# LiPoBattery.net
KiCad netlist of a schematic drawn in Altium Designer
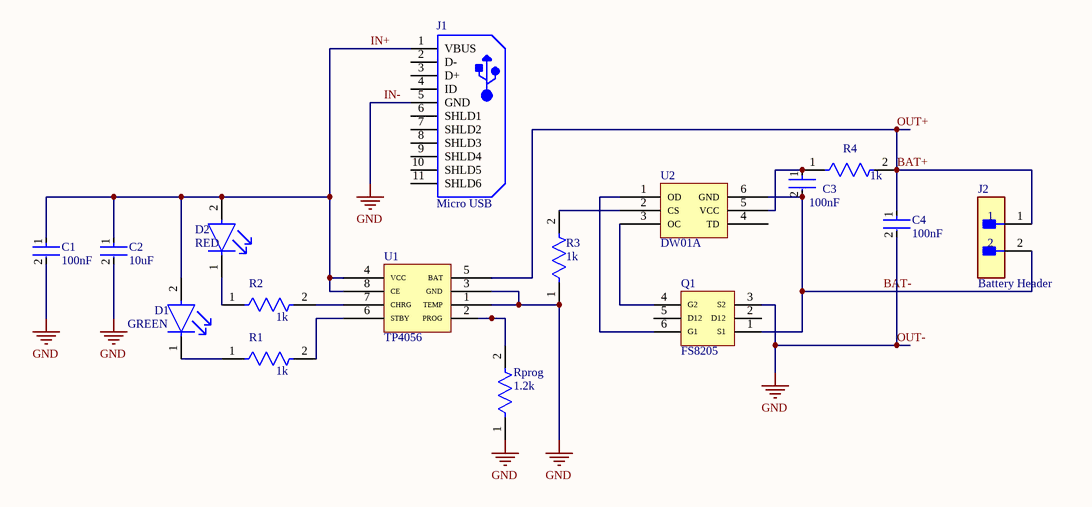
[diagram p0: LiPoBattery.SchDoc]

(export (version "E")
  (design (tool "Eeschema 10.0.6"))
  (components
    (comp (ref "C1")
      (value "100nF")
      (footprint "FP-CGA3E-0_3-0_1-IPC_B")
      (description "Cap Ceramic 100nF 25V X8R 20% Pad SMD 0603 +150°C Automotive T/R")
      (fields (field (name "TOLERANCE") "20%"))
      (libsource (lib "Altium Content Vault") (part "b4654b650e69147ec39a6b967a45e02"))
    )
    (comp (ref "C2")
      (value "10uF")
      (footprint "FP-CGA4J-IPC_B")
      (description "Cap Ceramic 10uF 10V X5R 20% Pad SMD 0805 +85°C Automotive T/R")
      (fields (field (name "TOLERANCE") "20%"))
      (libsource (lib "Altium Content Vault") (part "b4654b650e69147ec39a6b967a45e02"))
    )
    (comp (ref "C3")
      (value "100nF")
      (footprint "FP-CGA3E-0_3-0_1-IPC_B")
      (description "Cap Ceramic 100nF 25V X8R 20% Pad SMD 0603 +150°C Automotive T/R")
      (fields (field (name "TOLERANCE") "20%"))
      (libsource (lib "Altium Content Vault") (part "b4654b650e69147ec39a6b967a45e02"))
    )
    (comp (ref "C4")
      (value "100nF")
      (footprint "FP-CGA3E-0_3-0_1-IPC_B")
      (description "Cap Ceramic 100nF 25V X8R 20% Pad SMD 0603 +150°C Automotive T/R")
      (fields (field (name "TOLERANCE") "20%"))
      (libsource (lib "Altium Content Vault") (part "b4654b650e69147ec39a6b967a45e02"))
    )
    (comp (ref "D1")
      (value "GREEN")
      (footprint "FP-APHCM2012CGCK-F01-MFG")
      (description "LED GREEN CLEAR CHIP SMD")
      (libsource (lib "Altium Content Vault") (part "8706943c75ba83719d021d2fdc84c58"))
    )
    (comp (ref "D2")
      (value "RED")
      (footprint "FP-LTST-C190KRKT-MFG")
      (description "LED RED CLEAR CHIP SMD")
      (libsource (lib "Altium Content Vault") (part "8706943c75ba83719d021d2fdc84c58"))
    )
    (comp (ref "J1")
      (value "Micro USB")
      (footprint "FCI-10118193-0001LF-5_V")
      (description "Micro USB B Type Receptacle, -55 to 85 degC, 5-Pin SMD, RoHS, Tape and Reel")
      (fields (field (name "MANUFACTURER") "FCI"))
      (libsource (lib "Altium Content Vault") (part "USB-5-6SHLD"))
    )
    (comp (ref "J2")
      (value "Battery Header")
      (footprint "FP-B2B-PH-K_LF_SN-MFG")
      (description "Connector Header Through Hole 2 position 0.079\" (2.00mm)")
      (libsource (lib "Altium Content Vault") (part "3bc925449376181038e59eaffc5286c"))
    )
    (comp (ref "Q1")
      (value "FS8205")
      (footprint "SOT95P280X145-6N")
      (libsource (lib "LiPoBattery") (part "FS8205"))
    )
    (comp (ref "R1")
      (value "1k")
      (footprint "FP-CRGCQ0402-IPC_C")
      (description "CRGCQ0402 1KΩ 1% ±100ppm/°C 50V")
      (fields (field (name "MANUFACTURER PART NUMBER") "CRGCQ0402F1K0") (field (name "TOLERANCE") "0.01"))
      (libsource (lib "Altium Content Vault") (part "1029c3af85768c4190bb7ad29bc67b5"))
    )
    (comp (ref "R2")
      (value "1k")
      (footprint "FP-CRGCQ0402-IPC_C")
      (description "CRGCQ0402 1KΩ 1% ±100ppm/°C 50V")
      (fields (field (name "MANUFACTURER PART NUMBER") "CRGCQ0402F1K0") (field (name "TOLERANCE") "0.01"))
      (libsource (lib "Altium Content Vault") (part "1029c3af85768c4190bb7ad29bc67b5"))
    )
    (comp (ref "R3")
      (value "1k")
      (footprint "FP-CRGCQ0402-IPC_C")
      (description "CRGCQ0402 1KΩ 1% ±100ppm/°C 50V")
      (fields (field (name "MANUFACTURER PART NUMBER") "CRGCQ0402F1K0") (field (name "TOLERANCE") "0.01"))
      (libsource (lib "Altium Content Vault") (part "1029c3af85768c4190bb7ad29bc67b5"))
    )
    (comp (ref "R4")
      (value "1k")
      (footprint "FP-RNCP0402-IPC_A")
      (description "100Ω ±1% 0.1W 0402 High Power Anti-Sulfur Thin Film Chip Resistor")
      (fields (field (name "TOLERANCE") "1%"))
      (libsource (lib "Altium Content Vault") (part "1029c3af85768c4190bb7ad29bc67b5"))
    )
    (comp (ref "Rprog")
      (value "1.2k")
      (footprint "FP-MCU0805-MFG")
      (description "RES 1.05K OHM 0.5% 1/5W 0805")
      (fields (field (name "TOLERANCE") "1%"))
      (libsource (lib "Altium Content Vault") (part "1029c3af85768c4190bb7ad29bc67b5"))
    )
    (comp (ref "U1")
      (value "TP4056")
      (footprint "SOIC127P600X265-8N")
      (description "SOP-8 Battery Management ICs ROHS")
      (libsource (lib "LiPoBattery") (part "TP4056"))
    )
    (comp (ref "U2")
      (value "DW01A")
      (footprint "SOT95P280X145-6N")
      (description "battery protection IC")
      (libsource (lib "LiPoBattery") (part "DW01A"))
    )
  )
  (nets
    (net (code "1") (name "/BAT+") (class "Default")
      (node (ref "C4") (pin "1") (pinfunction "1_1") (pintype "passive"))
      (node (ref "J2") (pin "1") (pinfunction "1_1") (pintype "passive"))
      (node (ref "R4") (pin "2") (pinfunction "2_2") (pintype "passive"))
      (node (ref "U1") (pin "5") (pinfunction "BAT_5") (pintype "passive"))
    )
    (net (code "2") (name "/BAT-") (class "Default")
      (node (ref "C3") (pin "2") (pinfunction "2_2") (pintype "passive"))
      (node (ref "J2") (pin "2") (pinfunction "2_2") (pintype "passive"))
      (node (ref "Q1") (pin "1") (pinfunction "S1_1") (pintype "passive"))
      (node (ref "U2") (pin "6") (pinfunction "GND_6") (pintype "passive"))
    )
    (net (code "3") (name "/IN+") (class "Default")
      (node (ref "C1") (pin "1") (pinfunction "1_1") (pintype "passive"))
      (node (ref "C2") (pin "1") (pinfunction "1_1") (pintype "passive"))
      (node (ref "D1") (pin "2") (pinfunction "A_2") (pintype "passive"))
      (node (ref "D2") (pin "2") (pinfunction "A_2") (pintype "passive"))
      (node (ref "J1") (pin "1") (pinfunction "VBUS_1") (pintype "passive"))
      (node (ref "U1") (pin "4") (pinfunction "VCC_4") (pintype "passive"))
      (node (ref "U1") (pin "8") (pinfunction "CE_8") (pintype "passive"))
    )
    (net (code "4") (name "GND") (class "Default")
      (node (ref "C1") (pin "2") (pinfunction "2_2") (pintype "passive"))
      (node (ref "C2") (pin "2") (pinfunction "2_2") (pintype "passive"))
      (node (ref "C4") (pin "2") (pinfunction "2_2") (pintype "passive"))
      (node (ref "J1") (pin "5") (pinfunction "GND_5") (pintype "passive"))
      (node (ref "Q1") (pin "3") (pinfunction "S2_3") (pintype "passive"))
      (node (ref "R3") (pin "1") (pinfunction "1_1") (pintype "passive"))
      (node (ref "Rprog") (pin "1") (pinfunction "1_1") (pintype "passive"))
      (node (ref "U1") (pin "1") (pinfunction "TEMP_1") (pintype "passive"))
      (node (ref "U1") (pin "3") (pinfunction "GND_3") (pintype "passive"))
    )
    (net (code "5") (name "Net-(D1-C)") (class "Default")
      (node (ref "D1") (pin "1") (pinfunction "C_1") (pintype "passive"))
      (node (ref "R1") (pin "1") (pinfunction "1_1") (pintype "passive"))
    )
    (net (code "6") (name "Net-(D2-C)") (class "Default")
      (node (ref "D2") (pin "1") (pinfunction "C_1") (pintype "passive"))
      (node (ref "R2") (pin "1") (pinfunction "1_1") (pintype "passive"))
    )
    (net (code "7") (name "Net-(Q1-G1)") (class "Default")
      (node (ref "Q1") (pin "6") (pinfunction "G1_6") (pintype "passive"))
      (node (ref "U2") (pin "1") (pinfunction "OD_1") (pintype "passive"))
    )
    (net (code "8") (name "Net-(Q1-G2)") (class "Default")
      (node (ref "Q1") (pin "4") (pinfunction "G2_4") (pintype "passive"))
      (node (ref "U2") (pin "3") (pinfunction "OC_3") (pintype "passive"))
    )
    (net (code "9") (name "Net-(U1-CHRG)") (class "Default")
      (node (ref "R2") (pin "2") (pinfunction "2_2") (pintype "passive"))
      (node (ref "U1") (pin "7") (pinfunction "CHRG_7") (pintype "passive"))
    )
    (net (code "10") (name "Net-(U1-PROG)") (class "Default")
      (node (ref "Rprog") (pin "2") (pinfunction "2_2") (pintype "passive"))
      (node (ref "U1") (pin "2") (pinfunction "PROG_2") (pintype "passive"))
    )
    (net (code "11") (name "Net-(U1-STBY)") (class "Default")
      (node (ref "R1") (pin "2") (pinfunction "2_2") (pintype "passive"))
      (node (ref "U1") (pin "6") (pinfunction "STBY_6") (pintype "passive"))
    )
    (net (code "12") (name "Net-(U2-CS)") (class "Default")
      (node (ref "R3") (pin "2") (pinfunction "2_2") (pintype "passive"))
      (node (ref "U2") (pin "2") (pinfunction "CS_2") (pintype "passive"))
    )
    (net (code "13") (name "Net-(U2-VCC)") (class "Default")
      (node (ref "C3") (pin "1") (pinfunction "1_1") (pintype "passive"))
      (node (ref "R4") (pin "1") (pinfunction "1_1") (pintype "passive"))
      (node (ref "U2") (pin "5") (pinfunction "VCC_5") (pintype "passive"))
    )
    (net (code "14") (name "unconnected-(J1-D+-Pad3)") (class "Default")
      (node (ref "J1") (pin "3") (pinfunction "D+_3") (pintype "passive"))
    )
    (net (code "15") (name "unconnected-(J1-D--Pad2)") (class "Default")
      (node (ref "J1") (pin "2") (pinfunction "D-_2") (pintype "passive"))
    )
    (net (code "16") (name "unconnected-(J1-ID-Pad4)") (class "Default")
      (node (ref "J1") (pin "4") (pinfunction "ID_4") (pintype "passive"))
    )
    (net (code "17") (name "unconnected-(J1-SHLD1-Pad6)") (class "Default")
      (node (ref "J1") (pin "6") (pinfunction "SHLD1_6") (pintype "passive"))
    )
    (net (code "18") (name "unconnected-(J1-SHLD2-Pad7)") (class "Default")
      (node (ref "J1") (pin "7") (pinfunction "SHLD2_7") (pintype "passive"))
    )
    (net (code "19") (name "unconnected-(J1-SHLD3-Pad8)") (class "Default")
      (node (ref "J1") (pin "8") (pinfunction "SHLD3_8") (pintype "passive"))
    )
    (net (code "20") (name "unconnected-(J1-SHLD4-Pad9)") (class "Default")
      (node (ref "J1") (pin "9") (pinfunction "SHLD4_9") (pintype "passive"))
    )
    (net (code "21") (name "unconnected-(J1-SHLD5-Pad10)") (class "Default")
      (node (ref "J1") (pin "10") (pinfunction "SHLD5_10") (pintype "passive"))
    )
    (net (code "22") (name "unconnected-(J1-SHLD6-Pad11)") (class "Default")
      (node (ref "J1") (pin "11") (pinfunction "SHLD6_11") (pintype "passive"))
    )
    (net (code "23") (name "unconnected-(Q1-D12-Pad2)") (class "Default")
      (node (ref "Q1") (pin "2") (pinfunction "D12_2") (pintype "passive"))
    )
    (net (code "24") (name "unconnected-(Q1-D12-Pad5)") (class "Default")
      (node (ref "Q1") (pin "5") (pinfunction "D12_5") (pintype "passive"))
    )
    (net (code "25") (name "unconnected-(U2-TD-Pad4)") (class "Default")
      (node (ref "U2") (pin "4") (pinfunction "TD_4") (pintype "passive"))
    )
  )
)
